# PWR_stage.net
KiCad netlist of a schematic drawn in Altium Designer
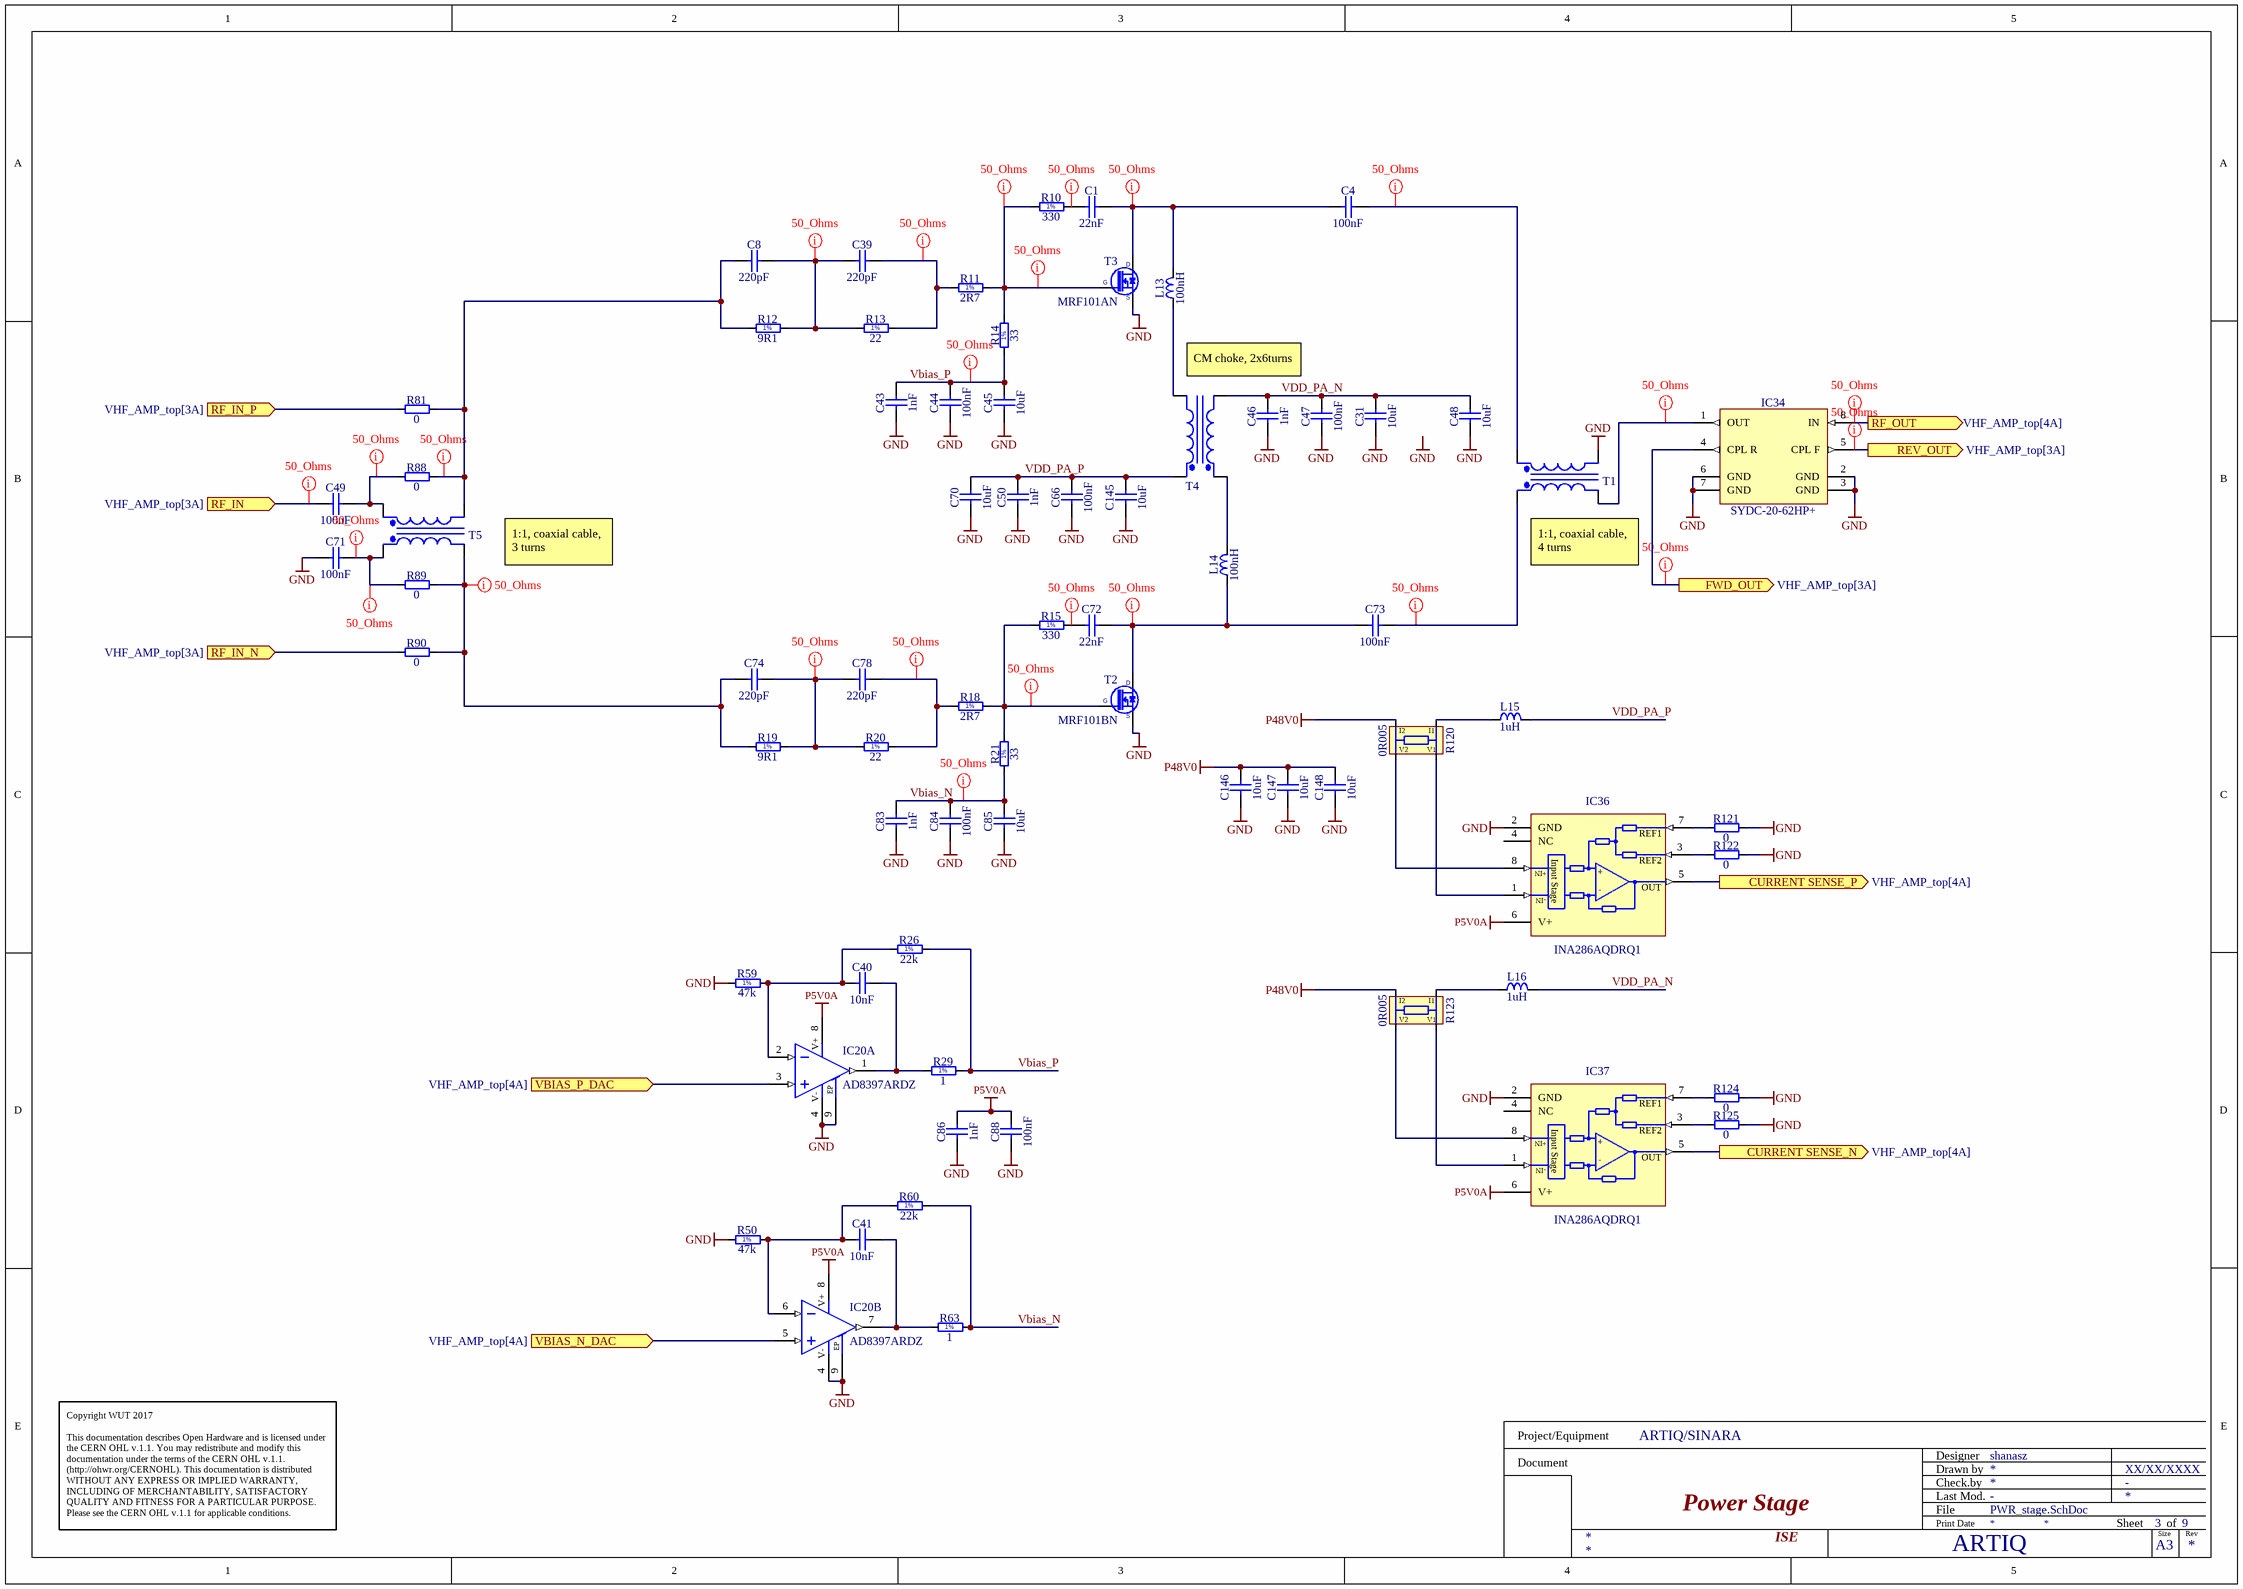
[diagram p0: PWR_stage.SchDoc]

(export (version "E")
  (design (tool "Eeschema 10.0.6"))
  (components
    (comp (ref "C1")
      (value "22nF")
      (footprint "CAPC2012X135N")
      (description "Non-polarised capacitor")
      (fields
        (field (name "PART NUMBER") "CC0805_22NF_50V_10%_X7R")
        (field (name "VOLTAGE") "50V")
        (field (name "AUTHOR") "CERN DEM JLC")
      )
      (libsource (lib "Capacitors") (part "Capacitor - non polarized"))
    )
    (comp (ref "C4")
      (value "100nF")
      (footprint "CAPC3216X140N")
      (description "Non-polarised capacitor")
      (fields
        (field (name "PART NUMBER") "CC1206_100NF_100V_10%_X7R")
        (field (name "VOLTAGE") "100V")
        (field (name "AUTHOR") "CERN DEM JLC")
      )
      (libsource (lib "Capacitors") (part "Capacitor - non polarized"))
    )
    (comp (ref "C8")
      (value "220pF")
      (footprint "CAPC2012X135N")
      (description "Non-polarised capacitor")
      (fields
        (field (name "PART NUMBER") "CC0805_220PF_50V_5%_C0G")
        (field (name "VOLTAGE") "50V")
        (field (name "AUTHOR") "CERN DEM JLC")
      )
      (libsource (lib "Capacitors") (part "Capacitor - non polarized"))
    )
    (comp (ref "C31")
      (value "10uF")
      (footprint "CAPC_TDK_CKG45N")
      (description "Non-polarised capacitor")
      (fields
        (field (name "PART NUMBER") "CC1812_10UF_100V_20%_X7S_TDK_CKG45N")
        (field (name "VOLTAGE") "100V")
        (field (name "AUTHOR") "CERN DEM MR")
      )
      (libsource (lib "Capacitors") (part "Capacitor - non polarized"))
    )
    (comp (ref "C39")
      (value "220pF")
      (footprint "CAPC2012X135N")
      (description "Non-polarised capacitor")
      (fields
        (field (name "PART NUMBER") "CC0805_220PF_50V_5%_C0G")
        (field (name "VOLTAGE") "50V")
        (field (name "AUTHOR") "CERN DEM JLC")
      )
      (libsource (lib "Capacitors") (part "Capacitor - non polarized"))
    )
    (comp (ref "C40")
      (value "10nF")
      (footprint "CAPC1005X55N")
      (description "Non-polarised capacitor")
      (fields
        (field (name "MANUFACTURER PART NUMBER") "CC0402_10NF_16V_10%_X7R")
        (field (name "MANUFACTURER") "GENERIC")
        (field (name "AUTHOR") "CERN DEM JLC")
      )
      (libsource (lib "Capacitors") (part "Capacitor - non polarized"))
    )
    (comp (ref "C41")
      (value "10nF")
      (footprint "CAPC1005X55N")
      (description "Non-polarised capacitor")
      (fields
        (field (name "MANUFACTURER PART NUMBER") "CC0402_10NF_16V_10%_X7R")
        (field (name "MANUFACTURER") "GENERIC")
        (field (name "AUTHOR") "CERN DEM JLC")
      )
      (libsource (lib "Capacitors") (part "Capacitor - non polarized"))
    )
    (comp (ref "C43")
      (value "1nF")
      (footprint "CAPC2012X135N")
      (description "Non-polarised capacitor")
      (fields
        (field (name "PART NUMBER") "CC0805_1NF_50V_5%_C0G")
        (field (name "VOLTAGE") "50V")
        (field (name "AUTHOR") "CERN DEM JLC")
      )
      (libsource (lib "Capacitors") (part "Capacitor - non polarized"))
    )
    (comp (ref "C44")
      (value "100nF")
      (footprint "CAPC3216X140N")
      (description "Non-polarised capacitor")
      (fields
        (field (name "PART NUMBER") "CC1206_100NF_100V_10%_X7R")
        (field (name "VOLTAGE") "100V")
        (field (name "AUTHOR") "CERN DEM JLC")
      )
      (libsource (lib "Capacitors") (part "Capacitor - non polarized"))
    )
    (comp (ref "C45")
      (value "10uF")
      (footprint "CAPC3225X280N")
      (description "Non-polarised capacitor")
      (fields
        (field (name "PART NUMBER") "CC1210_10UF_50V_10%_X7R_YUDEN_UMK325AB7106KMHP")
        (field (name "VOLTAGE") "50V")
        (field (name "AUTHOR") "CERN DEM JLC")
      )
      (libsource (lib "Capacitors") (part "Capacitor - non polarized"))
    )
    (comp (ref "C46")
      (value "1nF")
      (footprint "CAPC2012X135N")
      (description "Non-polarised capacitor")
      (fields
        (field (name "PART NUMBER") "CC0805_1NF_50V_5%_C0G")
        (field (name "VOLTAGE") "50V")
        (field (name "AUTHOR") "CERN DEM JLC")
      )
      (libsource (lib "Capacitors") (part "Capacitor - non polarized"))
    )
    (comp (ref "C47")
      (value "100nF")
      (footprint "CAPC3216X140N")
      (description "Non-polarised capacitor")
      (fields
        (field (name "PART NUMBER") "CC1206_100NF_100V_10%_X7R")
        (field (name "VOLTAGE") "100V")
        (field (name "AUTHOR") "CERN DEM JLC")
      )
      (libsource (lib "Capacitors") (part "Capacitor - non polarized"))
    )
    (comp (ref "C48")
      (value "10uF")
      (footprint "CAPC_TDK_CKG45N")
      (description "Non-polarised capacitor")
      (fields
        (field (name "PART NUMBER") "CC1812_10UF_100V_20%_X7S_TDK_CKG45N")
        (field (name "VOLTAGE") "100V")
        (field (name "AUTHOR") "CERN DEM MR")
      )
      (libsource (lib "Capacitors") (part "Capacitor - non polarized"))
    )
    (comp (ref "C49")
      (value "100nF")
      (footprint "CAPC2012X135N")
      (description "Non-polarised capacitor")
      (fields
        (field (name "PART NUMBER") "CC0805_100NF_50V_10%_X7R")
        (field (name "VOLTAGE") "50V")
        (field (name "AUTHOR") "CERN DEM JLC")
      )
      (libsource (lib "Capacitors") (part "Capacitor - non polarized"))
    )
    (comp (ref "C50")
      (value "1nF")
      (footprint "CAPC2012X135N")
      (description "Non-polarised capacitor")
      (fields
        (field (name "PART NUMBER") "CC0805_1NF_50V_5%_C0G")
        (field (name "VOLTAGE") "50V")
        (field (name "AUTHOR") "CERN DEM JLC")
      )
      (libsource (lib "Capacitors") (part "Capacitor - non polarized"))
    )
    (comp (ref "C66")
      (value "100nF")
      (footprint "CAPC3216X140N")
      (description "Non-polarised capacitor")
      (fields
        (field (name "PART NUMBER") "CC1206_100NF_100V_10%_X7R")
        (field (name "VOLTAGE") "100V")
        (field (name "AUTHOR") "CERN DEM JLC")
      )
      (libsource (lib "Capacitors") (part "Capacitor - non polarized"))
    )
    (comp (ref "C70")
      (value "10uF")
      (footprint "CAPC_TDK_CKG45N")
      (description "Non-polarised capacitor")
      (fields
        (field (name "PART NUMBER") "CC1812_10UF_100V_20%_X7S_TDK_CKG45N")
        (field (name "VOLTAGE") "100V")
        (field (name "AUTHOR") "CERN DEM MR")
      )
      (libsource (lib "Capacitors") (part "Capacitor - non polarized"))
    )
    (comp (ref "C71")
      (value "100nF")
      (footprint "CAPC2012X135N")
      (description "Non-polarised capacitor")
      (fields
        (field (name "PART NUMBER") "CC0805_100NF_50V_10%_X7R")
        (field (name "VOLTAGE") "50V")
        (field (name "AUTHOR") "CERN DEM JLC")
      )
      (libsource (lib "Capacitors") (part "Capacitor - non polarized"))
    )
    (comp (ref "C72")
      (value "22nF")
      (footprint "CAPC2012X135N")
      (description "Non-polarised capacitor")
      (fields
        (field (name "PART NUMBER") "CC0805_22NF_50V_10%_X7R")
        (field (name "VOLTAGE") "50V")
        (field (name "AUTHOR") "CERN DEM JLC")
      )
      (libsource (lib "Capacitors") (part "Capacitor - non polarized"))
    )
    (comp (ref "C73")
      (value "100nF")
      (footprint "CAPC3216X140N")
      (description "Non-polarised capacitor")
      (fields
        (field (name "PART NUMBER") "CC1206_100NF_100V_10%_X7R")
        (field (name "VOLTAGE") "100V")
        (field (name "AUTHOR") "CERN DEM JLC")
      )
      (libsource (lib "Capacitors") (part "Capacitor - non polarized"))
    )
    (comp (ref "C74")
      (value "220pF")
      (footprint "CAPC2012X135N")
      (description "Non-polarised capacitor")
      (fields
        (field (name "PART NUMBER") "CC0805_220PF_50V_5%_C0G")
        (field (name "VOLTAGE") "50V")
        (field (name "AUTHOR") "CERN DEM JLC")
      )
      (libsource (lib "Capacitors") (part "Capacitor - non polarized"))
    )
    (comp (ref "C78")
      (value "220pF")
      (footprint "CAPC2012X135N")
      (description "Non-polarised capacitor")
      (fields
        (field (name "PART NUMBER") "CC0805_220PF_50V_5%_C0G")
        (field (name "VOLTAGE") "50V")
        (field (name "AUTHOR") "CERN DEM JLC")
      )
      (libsource (lib "Capacitors") (part "Capacitor - non polarized"))
    )
    (comp (ref "C83")
      (value "1nF")
      (footprint "CAPC2012X135N")
      (description "Non-polarised capacitor")
      (fields
        (field (name "PART NUMBER") "CC0805_1NF_50V_5%_C0G")
        (field (name "VOLTAGE") "50V")
        (field (name "AUTHOR") "CERN DEM JLC")
      )
      (libsource (lib "Capacitors") (part "Capacitor - non polarized"))
    )
    (comp (ref "C84")
      (value "100nF")
      (footprint "CAPC3216X140N")
      (description "Non-polarised capacitor")
      (fields
        (field (name "PART NUMBER") "CC1206_100NF_100V_10%_X7R")
        (field (name "VOLTAGE") "100V")
        (field (name "AUTHOR") "CERN DEM JLC")
      )
      (libsource (lib "Capacitors") (part "Capacitor - non polarized"))
    )
    (comp (ref "C85")
      (value "10uF")
      (footprint "CAPC3225X280N")
      (description "Non-polarised capacitor")
      (fields
        (field (name "PART NUMBER") "CC1210_10UF_50V_10%_X7R_YUDEN_UMK325AB7106KMHP")
        (field (name "VOLTAGE") "50V")
        (field (name "AUTHOR") "CERN DEM JLC")
      )
      (libsource (lib "Capacitors") (part "Capacitor - non polarized"))
    )
    (comp (ref "C86")
      (value "1nF")
      (footprint "CAPC2012X135N")
      (description "Non-polarised capacitor")
      (fields
        (field (name "PART NUMBER") "CC0805_1NF_50V_5%_C0G")
        (field (name "VOLTAGE") "50V")
        (field (name "AUTHOR") "CERN DEM JLC")
      )
      (libsource (lib "Capacitors") (part "Capacitor - non polarized"))
    )
    (comp (ref "C88")
      (value "100nF")
      (footprint "CAPC2012X135N")
      (description "Non-polarised capacitor")
      (fields
        (field (name "PART NUMBER") "CC0805_100NF_50V_10%_X7R")
        (field (name "VOLTAGE") "50V")
        (field (name "AUTHOR") "CERN DEM JLC")
      )
      (libsource (lib "Capacitors") (part "Capacitor - non polarized"))
    )
    (comp (ref "C145")
      (value "10uF")
      (footprint "CAPC_TDK_CKG45N")
      (description "Non-polarised capacitor")
      (fields
        (field (name "PART NUMBER") "CC1812_10UF_100V_20%_X7S_TDK_CKG45N")
        (field (name "VOLTAGE") "100V")
        (field (name "AUTHOR") "CERN DEM MR")
      )
      (libsource (lib "Capacitors") (part "Capacitor - non polarized"))
    )
    (comp (ref "C146")
      (value "10uF")
      (footprint "CAPC_TDK_CKG45N")
      (description "Non-polarised capacitor")
      (fields
        (field (name "PART NUMBER") "CC1812_10UF_100V_20%_X7S_TDK_CKG45N")
        (field (name "VOLTAGE") "100V")
        (field (name "AUTHOR") "CERN DEM MR")
      )
      (libsource (lib "Capacitors") (part "Capacitor - non polarized"))
    )
    (comp (ref "C147")
      (value "10uF")
      (footprint "CAPC_TDK_CKG45N")
      (description "Non-polarised capacitor")
      (fields
        (field (name "PART NUMBER") "CC1812_10UF_100V_20%_X7S_TDK_CKG45N")
        (field (name "VOLTAGE") "100V")
        (field (name "AUTHOR") "CERN DEM MR")
      )
      (libsource (lib "Capacitors") (part "Capacitor - non polarized"))
    )
    (comp (ref "C148")
      (value "10uF")
      (footprint "CAPC_TDK_CKG45N")
      (description "Non-polarised capacitor")
      (fields
        (field (name "PART NUMBER") "CC1812_10UF_100V_20%_X7S_TDK_CKG45N")
        (field (name "VOLTAGE") "100V")
        (field (name "AUTHOR") "CERN DEM MR")
      )
      (libsource (lib "Capacitors") (part "Capacitor - non polarized"))
    )
    (comp (ref "IC20")
      (value "AD8397ARDZ")
      (footprint "SOIC127P600X175-9N-R241X309")
      (description "Dual Operational Amplifier With Exposed Pad")
      (fields (field (name "MANUFACTURER") "ANALOG DEVICES") (field (name "AUTHOR") "CERN DEM JLC"))
      (libsource (lib "ICs And Semiconductors") (part "Operational Amplifier x2 Type1 EP"))
    )
    (comp (ref "IC34")
      (value "SYDC-20-62HP+")
      (footprint "MINI-CIRCUITS_AH202-1")
      (description "50Ohm, 10 to 540MHz, 25W, 20dB Bi-Directional Coupler")
      (fields (field (name "MANUFACTURER") "MINI-CIRCUITS") (field (name "AUTHOR") "CERN DEM BC"))
      (libsource (lib "ICs And Semiconductors") (part "SYDC-20-62HP+"))
    )
    (comp (ref "IC36")
      (value "INA286AQDRQ1")
      (footprint "SOIC127P600X175-8N")
      (description "80V, Bi-Directional, Low-/High-Side, Voltage Output Current Sense Amplifier")
      (fields (field (name "MANUFACTURER") "TEXAS INSTRUMENTS") (field (name "AUTHOR") "CERN DEM JLC"))
      (libsource (lib "ICs And Semiconductors") (part "INA286"))
    )
    (comp (ref "IC37")
      (value "INA286AQDRQ1")
      (footprint "SOIC127P600X175-8N")
      (description "80V, Bi-Directional, Low-/High-Side, Voltage Output Current Sense Amplifier")
      (fields (field (name "MANUFACTURER") "TEXAS INSTRUMENTS") (field (name "AUTHOR") "CERN DEM JLC"))
      (libsource (lib "ICs And Semiconductors") (part "INA286"))
    )
    (comp (ref "L13")
      (value "100nH")
      (footprint "IND_COILCRAFT_1812SMS")
      (description "Inductor")
      (fields
        (field (name "PART NUMBER") "IND_100NH_5%_COILCRAFT_1812SMS-R10JLC")
        (field (name "POWER") "1.7A")
        (field (name "AUTHOR") "CERN DEM JLC")
      )
      (libsource (lib "Inductors & Transformers") (part "Inductor"))
    )
    (comp (ref "L14")
      (value "100nH")
      (footprint "IND_COILCRAFT_1812SMS")
      (description "Inductor")
      (fields
        (field (name "PART NUMBER") "IND_100NH_5%_COILCRAFT_1812SMS-R10JLC")
        (field (name "POWER") "1.7A")
        (field (name "AUTHOR") "CERN DEM JLC")
      )
      (libsource (lib "Inductors & Transformers") (part "Inductor"))
    )
    (comp (ref "L15")
      (value "1uH")
      (footprint "IND_BOURNS_SRN3015")
      (description "Inductor")
      (fields
        (field (name "PART NUMBER") "IND_1UH_30%_BOURNS_SRN3015")
        (field (name "POWER") "2.35A")
        (field (name "AUTHOR") "CERN DEM JLC")
      )
      (libsource (lib "") (part "Inductor_1"))
    )
    (comp (ref "L16")
      (value "1uH")
      (footprint "IND_BOURNS_SRN3015")
      (description "Inductor")
      (fields
        (field (name "PART NUMBER") "IND_1UH_30%_BOURNS_SRN3015")
        (field (name "POWER") "2.35A")
        (field (name "AUTHOR") "CERN DEM JLC")
      )
      (libsource (lib "") (part "Inductor_1"))
    )
    (comp (ref "R10")
      (value "330")
      (footprint "RESC2012X60N")
      (description "Resistor - 1%")
      (fields
        (field (name "PART NUMBER") "R0805_330R_1%_0.125W_100PPM")
        (field (name "POWER") "0.125W")
        (field (name "AUTHOR") "CERN DEM JLC")
      )
      (libsource (lib "Resistors") (part "Resistor - 1%"))
    )
    (comp (ref "R11")
      (value "2R7")
      (footprint "RESC2012X60N")
      (description "Resistor - 1%")
      (fields
        (field (name "PART NUMBER") "R0805_2R7_1%_0.125W_200PPM")
        (field (name "POWER") "0.125W")
        (field (name "AUTHOR") "CERN DEM JLC")
      )
      (libsource (lib "Resistors") (part "Resistor - 1%"))
    )
    (comp (ref "R12")
      (value "9R1")
      (footprint "RESC2012X60N")
      (description "Resistor - 1%")
      (fields
        (field (name "PART NUMBER") "R0805_9R1_1%_0.125W_200PPM")
        (field (name "POWER") "0.125W")
        (field (name "AUTHOR") "CERN DEM JLC")
      )
      (libsource (lib "Resistors") (part "Resistor - 1%"))
    )
    (comp (ref "R13")
      (value "22")
      (footprint "RESC2012X60N")
      (description "Resistor - 1%")
      (fields
        (field (name "PART NUMBER") "R0805_22R_1%_0.125W_100PPM")
        (field (name "POWER") "0.125W")
        (field (name "AUTHOR") "CERN DEM JLC")
      )
      (libsource (lib "Resistors") (part "Resistor - 1%"))
    )
    (comp (ref "R14")
      (value "33")
      (footprint "RESC2012X60N")
      (description "Resistor - 1%")
      (fields
        (field (name "PART NUMBER") "R0805_33R_1%_0.125W_100PPM")
        (field (name "POWER") "0.125W")
        (field (name "AUTHOR") "CERN DEM JLC")
      )
      (libsource (lib "Resistors") (part "Resistor - 1%"))
    )
    (comp (ref "R15")
      (value "330")
      (footprint "RESC2012X60N")
      (description "Resistor - 1%")
      (fields
        (field (name "PART NUMBER") "R0805_330R_1%_0.125W_100PPM")
        (field (name "POWER") "0.125W")
        (field (name "AUTHOR") "CERN DEM JLC")
      )
      (libsource (lib "Resistors") (part "Resistor - 1%"))
    )
    (comp (ref "R18")
      (value "2R7")
      (footprint "RESC2012X60N")
      (description "Resistor - 1%")
      (fields
        (field (name "PART NUMBER") "R0805_2R7_1%_0.125W_200PPM")
        (field (name "POWER") "0.125W")
        (field (name "AUTHOR") "CERN DEM JLC")
      )
      (libsource (lib "Resistors") (part "Resistor - 1%"))
    )
    (comp (ref "R19")
      (value "9R1")
      (footprint "RESC2012X60N")
      (description "Resistor - 1%")
      (fields
        (field (name "PART NUMBER") "R0805_9R1_1%_0.125W_200PPM")
        (field (name "POWER") "0.125W")
        (field (name "AUTHOR") "CERN DEM JLC")
      )
      (libsource (lib "Resistors") (part "Resistor - 1%"))
    )
    (comp (ref "R20")
      (value "22")
      (footprint "RESC2012X60N")
      (description "Resistor - 1%")
      (fields
        (field (name "PART NUMBER") "R0805_22R_1%_0.125W_100PPM")
        (field (name "POWER") "0.125W")
        (field (name "AUTHOR") "CERN DEM JLC")
      )
      (libsource (lib "Resistors") (part "Resistor - 1%"))
    )
    (comp (ref "R21")
      (value "33")
      (footprint "RESC2012X60N")
      (description "Resistor - 1%")
      (fields
        (field (name "PART NUMBER") "R0805_33R_1%_0.125W_100PPM")
        (field (name "POWER") "0.125W")
        (field (name "AUTHOR") "CERN DEM JLC")
      )
      (libsource (lib "Resistors") (part "Resistor - 1%"))
    )
    (comp (ref "R26")
      (value "22k")
      (footprint "RESC1005X40N")
      (description "Resistor - 1%")
      (fields
        (field (name "PART NUMBER") "R0402_22K_1%_0.0625W_100PPM")
        (field (name "POWER") "0.0625W")
        (field (name "AUTHOR") "CERN DEM JLC")
      )
      (libsource (lib "Resistors") (part "Resistor - 1%"))
    )
    (comp (ref "R29")
      (value "1")
      (footprint "RESC1005X40N")
      (description "Resistor - 1%")
      (fields
        (field (name "PART NUMBER") "R0402_1R_1%_0.0625W_200PPM")
        (field (name "POWER") "0.0625W")
        (field (name "AUTHOR") "CERN DEM JLC")
      )
      (libsource (lib "Resistors") (part "Resistor - 1%"))
    )
    (comp (ref "R50")
      (value "47k")
      (footprint "RESC1005X40N")
      (description "Resistor - 1%")
      (fields
        (field (name "PART NUMBER") "R0402_47K_1%_0.0625W_100PPM")
        (field (name "POWER") "0.0625W")
        (field (name "AUTHOR") "CERN DEM JLC")
      )
      (libsource (lib "Resistors") (part "Resistor - 1%"))
    )
    (comp (ref "R59")
      (value "47k")
      (footprint "RESC1005X40N")
      (description "Resistor - 1%")
      (fields
        (field (name "PART NUMBER") "R0402_47K_1%_0.0625W_100PPM")
        (field (name "POWER") "0.0625W")
        (field (name "AUTHOR") "CERN DEM JLC")
      )
      (libsource (lib "Resistors") (part "Resistor - 1%"))
    )
    (comp (ref "R60")
      (value "22k")
      (footprint "RESC1005X40N")
      (description "Resistor - 1%")
      (fields
        (field (name "PART NUMBER") "R0402_22K_1%_0.0625W_100PPM")
        (field (name "POWER") "0.0625W")
        (field (name "AUTHOR") "CERN DEM JLC")
      )
      (libsource (lib "Resistors") (part "Resistor - 1%"))
    )
    (comp (ref "R63")
      (value "1")
      (footprint "RESC1005X40N")
      (description "Resistor - 1%")
      (fields
        (field (name "PART NUMBER") "R0402_1R_1%_0.0625W_200PPM")
        (field (name "POWER") "0.0625W")
        (field (name "AUTHOR") "CERN DEM JLC")
      )
      (libsource (lib "Resistors") (part "Resistor - 1%"))
    )
    (comp (ref "R81")
      (value "0")
      (footprint "RESC2012X60N")
      (description "Resistor")
      (fields
        (field (name "PART NUMBER") "R0805_0R_JUMPER")
        (field (name "MANUFACTURER") "GENERIC")
        (field (name "AUTHOR") "CERN DEM JLC")
      )
      (libsource (lib "Resistors") (part "Resistor"))
    )
    (comp (ref "R88")
      (value "0")
      (footprint "RESC2012X60N")
      (description "Resistor")
      (fields
        (field (name "PART NUMBER") "R0805_0R_JUMPER")
        (field (name "MANUFACTURER") "GENERIC")
        (field (name "AUTHOR") "CERN DEM JLC")
      )
      (libsource (lib "Resistors") (part "Resistor"))
    )
    (comp (ref "R89")
      (value "0")
      (footprint "RESC2012X60N")
      (description "Resistor")
      (fields
        (field (name "PART NUMBER") "R0805_0R_JUMPER")
        (field (name "MANUFACTURER") "GENERIC")
        (field (name "AUTHOR") "CERN DEM JLC")
      )
      (libsource (lib "Resistors") (part "Resistor"))
    )
    (comp (ref "R90")
      (value "0")
      (footprint "RESC2012X60N")
      (description "Resistor")
      (fields
        (field (name "PART NUMBER") "R0805_0R_JUMPER")
        (field (name "MANUFACTURER") "GENERIC")
        (field (name "AUTHOR") "CERN DEM JLC")
      )
      (libsource (lib "Resistors") (part "Resistor"))
    )
    (comp (ref "R120")
      (value "0R005")
      (footprint "RES_OHMITE_LVK25")
      (description "Power and Current Sensing Resistor")
      (fields
        (field (name "PART NUMBER") "R_0R005_0.5%_2W_100PPM_OHMITE_LVK25")
        (field (name "POWER") "2W")
        (field (name "AUTHOR") "CERN DEM JLC")
      )
      (libsource (lib "Resistors") (part "Current + Voltage Sense Resistor"))
    )
    (comp (ref "R121")
      (value "0")
      (footprint "RESC2012X60N")
      (description "Resistor")
      (fields
        (field (name "PART NUMBER") "R0805_0R_JUMPER")
        (field (name "MANUFACTURER") "GENERIC")
        (field (name "AUTHOR") "CERN DEM JLC")
      )
      (libsource (lib "Resistors") (part "Resistor"))
    )
    (comp (ref "R122")
      (value "0")
      (footprint "RESC2012X60N")
      (description "Resistor")
      (fields
        (field (name "PART NUMBER") "R0805_0R_JUMPER")
        (field (name "MANUFACTURER") "GENERIC")
        (field (name "AUTHOR") "CERN DEM JLC")
      )
      (libsource (lib "Resistors") (part "Resistor"))
    )
    (comp (ref "R123")
      (value "0R005")
      (footprint "RES_OHMITE_LVK25")
      (description "Power and Current Sensing Resistor")
      (fields
        (field (name "PART NUMBER") "R_0R005_0.5%_2W_100PPM_OHMITE_LVK25")
        (field (name "POWER") "2W")
        (field (name "AUTHOR") "CERN DEM JLC")
      )
      (libsource (lib "Resistors") (part "Current + Voltage Sense Resistor"))
    )
    (comp (ref "R124")
      (value "0")
      (footprint "RESC2012X60N")
      (description "Resistor")
      (fields
        (field (name "PART NUMBER") "R0805_0R_JUMPER")
        (field (name "MANUFACTURER") "GENERIC")
        (field (name "AUTHOR") "CERN DEM JLC")
      )
      (libsource (lib "Resistors") (part "Resistor"))
    )
    (comp (ref "R125")
      (value "0")
      (footprint "RESC2012X60N")
      (description "Resistor")
      (fields
        (field (name "PART NUMBER") "R0805_0R_JUMPER")
        (field (name "MANUFACTURER") "GENERIC")
        (field (name "AUTHOR") "CERN DEM JLC")
      )
      (libsource (lib "Resistors") (part "Resistor"))
    )
    (comp (ref "T1")
      (value "Trans Ideal")
      (footprint "Balun_5961000601")
      (description "Transformer (Ideal)")
      (fields (field (name "PUBLISHER") "Altium Limited"))
      (libsource (lib "") (part "Balun_coaxialcable_1"))
    )
    (comp (ref "T2")
      (value "MRF101BN")
      (footprint "TO-220-HFLIP")
      (description "N-CHANNEL MOSFET WITH DIODE")
      (fields
        (field (name "PART NUMBER") "MRF101BN_hflip")
        (field (name "MANUFACTURER") "NXP SEMICONDUCTORS")
        (field (name "AUTHOR") "CERN DEM HF")
      )
      (libsource (lib "ICs And Semiconductors") (part "N-MOSFET-D 1D 2S 3G"))
    )
    (comp (ref "T3")
      (value "MRF101AN")
      (footprint "TO-220-HFLIP")
      (description "N-CHANNEL MOSFET WITH DIODE")
      (fields
        (field (name "PART NUMBER") "MRF101AN_hflip")
        (field (name "MANUFACTURER") "NXP SEMICONDUCTORS")
        (field (name "AUTHOR") "CERN DEM HF")
      )
      (libsource (lib "ICs And Semiconductors") (part "N-MOSFET-D 1G 2S 3D"))
    )
    (comp (ref "T4")
      (value "Trans Ideal")
      (footprint "Balun_5961000601_power")
      (description "Transformer (Ideal)")
      (fields (field (name "PUBLISHER") "Altium Limited"))
      (libsource (lib "VHF_AMP_lib") (part "Balun_coaxialcable"))
    )
    (comp (ref "T5")
      (value "Trans Ideal")
      (footprint "Balun_5943001101")
      (description "Transformer (Ideal)")
      (fields (field (name "PUBLISHER") "Altium Limited"))
      (libsource (lib "") (part "Balun_coaxialcable_1"))
    )
  )
  (nets
    (net (code "1") (name "/CURRENT SENSE_N") (class "Default")
      (node (ref "IC37") (pin "5") (pinfunction "OUT_5") (pintype "output"))
    )
    (net (code "2") (name "/CURRENT SENSE_P") (class "Default")
      (node (ref "IC36") (pin "5") (pinfunction "OUT_5") (pintype "output"))
    )
    (net (code "3") (name "/FWD_OUT") (class "Default")
      (node (ref "IC34") (pin "4") (pinfunction "CPL_R_4") (pintype "output"))
    )
    (net (code "4") (name "/REV_OUT") (class "Default")
      (node (ref "IC34") (pin "5") (pinfunction "CPL_F_5") (pintype "output"))
    )
    (net (code "5") (name "/RF_IN") (class "Default")
      (node (ref "C49") (pin "1") (pinfunction "1_1") (pintype "passive"))
    )
    (net (code "6") (name "/RF_IN_N") (class "Default")
      (node (ref "R90") (pin "1") (pinfunction "1_1") (pintype "passive"))
    )
    (net (code "7") (name "/RF_IN_P") (class "Default")
      (node (ref "R81") (pin "1") (pinfunction "1_1") (pintype "passive"))
    )
    (net (code "8") (name "/RF_OUT") (class "Default")
      (node (ref "IC34") (pin "8") (pinfunction "IN_8") (pintype "input"))
    )
    (net (code "9") (name "/VBIAS_N_DAC") (class "Default")
      (node (ref "IC20") (pin "5") (pinfunction "IN+_5") (pintype "input"))
    )
    (net (code "10") (name "/VBIAS_P_DAC") (class "Default")
      (node (ref "IC20") (pin "3") (pinfunction "IN+_3") (pintype "input"))
    )
    (net (code "11") (name "/VDD_PA_N") (class "Default")
      (node (ref "C31") (pin "2") (pinfunction "2_2") (pintype "passive"))
      (node (ref "C46") (pin "2") (pinfunction "2_2") (pintype "passive"))
      (node (ref "C47") (pin "2") (pinfunction "2_2") (pintype "passive"))
      (node (ref "C48") (pin "2") (pinfunction "2_2") (pintype "passive"))
      (node (ref "L16") (pin "2") (pinfunction "2_2") (pintype "passive"))
      (node (ref "T4") (pin "2") (pinfunction "Pri-_2") (pintype "passive"))
    )
    (net (code "12") (name "/VDD_PA_P") (class "Default")
      (node (ref "C145") (pin "2") (pinfunction "2_2") (pintype "passive"))
      (node (ref "C50") (pin "2") (pinfunction "2_2") (pintype "passive"))
      (node (ref "C66") (pin "2") (pinfunction "2_2") (pintype "passive"))
      (node (ref "C70") (pin "2") (pinfunction "2_2") (pintype "passive"))
      (node (ref "L15") (pin "2") (pinfunction "2_2") (pintype "passive"))
      (node (ref "T4") (pin "3") (pinfunction "Sec+_3") (pintype "passive"))
    )
    (net (code "13") (name "/Vbias_N") (class "Default")
      (node (ref "C83") (pin "2") (pinfunction "2_2") (pintype "passive"))
      (node (ref "C84") (pin "2") (pinfunction "2_2") (pintype "passive"))
      (node (ref "C85") (pin "2") (pinfunction "2_2") (pintype "passive"))
      (node (ref "R21") (pin "1") (pinfunction "1_1") (pintype "passive"))
      (node (ref "R60") (pin "1") (pinfunction "1_1") (pintype "passive"))
      (node (ref "R63") (pin "2") (pinfunction "2_2") (pintype "passive"))
    )
    (net (code "14") (name "/Vbias_P") (class "Default")
      (node (ref "C43") (pin "2") (pinfunction "2_2") (pintype "passive"))
      (node (ref "C44") (pin "2") (pinfunction "2_2") (pintype "passive"))
      (node (ref "C45") (pin "2") (pinfunction "2_2") (pintype "passive"))
      (node (ref "R14") (pin "1") (pinfunction "1_1") (pintype "passive"))
      (node (ref "R26") (pin "1") (pinfunction "1_1") (pintype "passive"))
      (node (ref "R29") (pin "2") (pinfunction "2_2") (pintype "passive"))
    )
    (net (code "15") (name "GND") (class "Default")
      (node (ref "C145") (pin "1") (pinfunction "1_1") (pintype "passive"))
      (node (ref "C146") (pin "1") (pinfunction "1_1") (pintype "passive"))
      (node (ref "C147") (pin "1") (pinfunction "1_1") (pintype "passive"))
      (node (ref "C148") (pin "1") (pinfunction "1_1") (pintype "passive"))
      (node (ref "C31") (pin "1") (pinfunction "1_1") (pintype "passive"))
      (node (ref "C43") (pin "1") (pinfunction "1_1") (pintype "passive"))
      (node (ref "C44") (pin "1") (pinfunction "1_1") (pintype "passive"))
      (node (ref "C45") (pin "1") (pinfunction "1_1") (pintype "passive"))
      (node (ref "C46") (pin "1") (pinfunction "1_1") (pintype "passive"))
      (node (ref "C47") (pin "1") (pinfunction "1_1") (pintype "passive"))
      (node (ref "C48") (pin "1") (pinfunction "1_1") (pintype "passive"))
      (node (ref "C50") (pin "1") (pinfunction "1_1") (pintype "passive"))
      (node (ref "C66") (pin "1") (pinfunction "1_1") (pintype "passive"))
      (node (ref "C70") (pin "1") (pinfunction "1_1") (pintype "passive"))
      (node (ref "C71") (pin "1") (pinfunction "1_1") (pintype "passive"))
      (node (ref "C83") (pin "1") (pinfunction "1_1") (pintype "passive"))
      (node (ref "C84") (pin "1") (pinfunction "1_1") (pintype "passive"))
      (node (ref "C85") (pin "1") (pinfunction "1_1") (pintype "passive"))
      (node (ref "C86") (pin "1") (pinfunction "1_1") (pintype "passive"))
      (node (ref "C88") (pin "1") (pinfunction "1_1") (pintype "passive"))
      (node (ref "IC20") (pin "4") (pinfunction "V-_4") (pintype "power_in"))
      (node (ref "IC20") (pin "9") (pinfunction "Exposed_Pad_9") (pintype "power_in"))
      (node (ref "IC34") (pin "2") (pinfunction "GND_2") (pintype "power_in"))
      (node (ref "IC34") (pin "3") (pinfunction "GND_3") (pintype "power_in"))
      (node (ref "IC34") (pin "6") (pinfunction "GND_6") (pintype "power_in"))
      (node (ref "IC34") (pin "7") (pinfunction "GND_7") (pintype "power_in"))
      (node (ref "IC36") (pin "2") (pinfunction "GND_2") (pintype "power_in"))
      (node (ref "IC37") (pin "2") (pinfunction "GND_2") (pintype "power_in"))
      (node (ref "R121") (pin "2") (pinfunction "2_2") (pintype "passive"))
      (node (ref "R122") (pin "2") (pinfunction "2_2") (pintype "passive"))
      (node (ref "R124") (pin "2") (pinfunction "2_2") (pintype "passive"))
      (node (ref "R125") (pin "2") (pinfunction "2_2") (pintype "passive"))
      (node (ref "R50") (pin "2") (pinfunction "2_2") (pintype "passive"))
      (node (ref "R59") (pin "2") (pinfunction "2_2") (pintype "passive"))
      (node (ref "T1") (pin "2") (pinfunction "Pri-_2") (pintype "passive"))
      (node (ref "T2") (pin "2") (pinfunction "S_2") (pintype "passive"))
      (node (ref "T3") (pin "2") (pinfunction "S_2") (pintype "passive"))
    )
    (net (code "16") (name "Net-(C1-Pad1)") (class "Default")
      (node (ref "C1") (pin "1") (pinfunction "1_1") (pintype "passive"))
      (node (ref "R10") (pin "2") (pinfunction "2_2") (pintype "passive"))
    )
    (net (code "17") (name "Net-(C39-Pad1)") (class "Default")
      (node (ref "C39") (pin "1") (pinfunction "1_1") (pintype "passive"))
      (node (ref "C8") (pin "2") (pinfunction "2_2") (pintype "passive"))
      (node (ref "R12") (pin "2") (pinfunction "2_2") (pintype "passive"))
      (node (ref "R13") (pin "1") (pinfunction "1_1") (pintype "passive"))
    )
    (net (code "18") (name "Net-(C39-Pad2)") (class "Default")
      (node (ref "C39") (pin "2") (pinfunction "2_2") (pintype "passive"))
      (node (ref "R11") (pin "1") (pinfunction "1_1") (pintype "passive"))
      (node (ref "R13") (pin "2") (pinfunction "2_2") (pintype "passive"))
    )
    (net (code "19") (name "Net-(C72-Pad1)") (class "Default")
      (node (ref "C72") (pin "1") (pinfunction "1_1") (pintype "passive"))
      (node (ref "R15") (pin "2") (pinfunction "2_2") (pintype "passive"))
    )
    (net (code "20") (name "Net-(C74-Pad2)") (class "Default")
      (node (ref "C74") (pin "2") (pinfunction "2_2") (pintype "passive"))
      (node (ref "C78") (pin "1") (pinfunction "1_1") (pintype "passive"))
      (node (ref "R19") (pin "2") (pinfunction "2_2") (pintype "passive"))
      (node (ref "R20") (pin "1") (pinfunction "1_1") (pintype "passive"))
    )
    (net (code "21") (name "Net-(C78-Pad2)") (class "Default")
      (node (ref "C78") (pin "2") (pinfunction "2_2") (pintype "passive"))
      (node (ref "R18") (pin "1") (pinfunction "1_1") (pintype "passive"))
      (node (ref "R20") (pin "2") (pinfunction "2_2") (pintype "passive"))
    )
    (net (code "22") (name "Net-(IC20A-IN-)") (class "Default")
      (node (ref "C40") (pin "1") (pinfunction "1_1") (pintype "passive"))
      (node (ref "IC20") (pin "2") (pinfunction "IN-_2") (pintype "input"))
      (node (ref "R26") (pin "2") (pinfunction "2_2") (pintype "passive"))
      (node (ref "R59") (pin "1") (pinfunction "1_1") (pintype "passive"))
    )
    (net (code "23") (name "Net-(IC20A-OUT)") (class "Default")
      (node (ref "C40") (pin "2") (pinfunction "2_2") (pintype "passive"))
      (node (ref "IC20") (pin "1") (pinfunction "OUT_1") (pintype "output"))
      (node (ref "R29") (pin "1") (pinfunction "1_1") (pintype "passive"))
    )
    (net (code "24") (name "Net-(IC20B-IN-)") (class "Default")
      (node (ref "C41") (pin "1") (pinfunction "1_1") (pintype "passive"))
      (node (ref "IC20") (pin "6") (pinfunction "IN-_6") (pintype "input"))
      (node (ref "R50") (pin "1") (pinfunction "1_1") (pintype "passive"))
      (node (ref "R60") (pin "2") (pinfunction "2_2") (pintype "passive"))
    )
    (net (code "25") (name "Net-(IC20B-OUT)") (class "Default")
      (node (ref "C41") (pin "2") (pinfunction "2_2") (pintype "passive"))
      (node (ref "IC20") (pin "7") (pinfunction "OUT_7") (pintype "output"))
      (node (ref "R63") (pin "1") (pinfunction "1_1") (pintype "passive"))
    )
    (net (code "26") (name "Net-(IC34-OUT)") (class "Default")
      (node (ref "IC34") (pin "1") (pinfunction "OUT_1") (pintype "output"))
      (node (ref "T1") (pin "4") (pinfunction "Sec-_4") (pintype "passive"))
    )
    (net (code "27") (name "Net-(IC36-+IN)") (class "Default")
      (node (ref "IC36") (pin "8") (pinfunction "+IN_8") (pintype "input"))
      (node (ref "R120") (pin "V2") (pinfunction "V2_V2") (pintype "passive"))
    )
    (net (code "28") (name "Net-(IC36--IN)") (class "Default")
      (node (ref "IC36") (pin "1") (pinfunction "-IN_1") (pintype "input"))
      (node (ref "R120") (pin "V1") (pinfunction "V1_V1") (pintype "passive"))
    )
    (net (code "29") (name "Net-(IC36-REF1)") (class "Default")
      (node (ref "IC36") (pin "7") (pinfunction "REF1_7") (pintype "input"))
      (node (ref "R121") (pin "1") (pinfunction "1_1") (pintype "passive"))
    )
    (net (code "30") (name "Net-(IC36-REF2)") (class "Default")
      (node (ref "IC36") (pin "3") (pinfunction "REF2_3") (pintype "input"))
      (node (ref "R122") (pin "1") (pinfunction "1_1") (pintype "passive"))
    )
    (net (code "31") (name "Net-(IC37-+IN)") (class "Default")
      (node (ref "IC37") (pin "8") (pinfunction "+IN_8") (pintype "input"))
      (node (ref "R123") (pin "V2") (pinfunction "V2_V2") (pintype "passive"))
    )
    (net (code "32") (name "Net-(IC37--IN)") (class "Default")
      (node (ref "IC37") (pin "1") (pinfunction "-IN_1") (pintype "input"))
      (node (ref "R123") (pin "V1") (pinfunction "V1_V1") (pintype "passive"))
    )
    (net (code "33") (name "Net-(IC37-REF1)") (class "Default")
      (node (ref "IC37") (pin "7") (pinfunction "REF1_7") (pintype "input"))
      (node (ref "R124") (pin "1") (pinfunction "1_1") (pintype "passive"))
    )
    (net (code "34") (name "Net-(IC37-REF2)") (class "Default")
      (node (ref "IC37") (pin "3") (pinfunction "REF2_3") (pintype "input"))
      (node (ref "R125") (pin "1") (pinfunction "1_1") (pintype "passive"))
    )
    (net (code "35") (name "Net-(L15-Pad1)") (class "Default")
      (node (ref "L15") (pin "1") (pinfunction "1_1") (pintype "passive"))
      (node (ref "R120") (pin "I1") (pinfunction "I1_I1") (pintype "passive"))
    )
    (net (code "36") (name "Net-(L16-Pad1)") (class "Default")
      (node (ref "L16") (pin "1") (pinfunction "1_1") (pintype "passive"))
      (node (ref "R123") (pin "I1") (pinfunction "I1_I1") (pintype "passive"))
    )
    (net (code "37") (name "Net-(T1-Pri+)") (class "Default")
      (node (ref "C4") (pin "2") (pinfunction "2_2") (pintype "passive"))
      (node (ref "T1") (pin "1") (pinfunction "Pri+_1") (pintype "passive"))
    )
    (net (code "38") (name "Net-(T1-Sec+)") (class "Default")
      (node (ref "C73") (pin "2") (pinfunction "2_2") (pintype "passive"))
      (node (ref "T1") (pin "3") (pinfunction "Sec+_3") (pintype "passive"))
    )
    (net (code "39") (name "Net-(T2-D)") (class "Default")
      (node (ref "C72") (pin "2") (pinfunction "2_2") (pintype "passive"))
      (node (ref "C73") (pin "1") (pinfunction "1_1") (pintype "passive"))
      (node (ref "L14") (pin "1") (pinfunction "1_1") (pintype "passive"))
      (node (ref "T2") (pin "1") (pinfunction "D_1") (pintype "passive"))
    )
    (net (code "40") (name "Net-(T2-G)") (class "Default")
      (node (ref "R15") (pin "1") (pinfunction "1_1") (pintype "passive"))
      (node (ref "R18") (pin "2") (pinfunction "2_2") (pintype "passive"))
      (node (ref "R21") (pin "2") (pinfunction "2_2") (pintype "passive"))
      (node (ref "T2") (pin "3") (pinfunction "G_3") (pintype "passive"))
    )
    (net (code "41") (name "Net-(T3-D)") (class "Default")
      (node (ref "C1") (pin "2") (pinfunction "2_2") (pintype "passive"))
      (node (ref "C4") (pin "1") (pinfunction "1_1") (pintype "passive"))
      (node (ref "L13") (pin "2") (pinfunction "2_2") (pintype "passive"))
      (node (ref "T3") (pin "3") (pinfunction "D_3") (pintype "passive"))
    )
    (net (code "42") (name "Net-(T3-G)") (class "Default")
      (node (ref "R10") (pin "1") (pinfunction "1_1") (pintype "passive"))
      (node (ref "R11") (pin "2") (pinfunction "2_2") (pintype "passive"))
      (node (ref "R14") (pin "2") (pinfunction "2_2") (pintype "passive"))
      (node (ref "T3") (pin "1") (pinfunction "G_1") (pintype "passive"))
    )
    (net (code "43") (name "Net-(T4-Pri+)") (class "Default")
      (node (ref "L14") (pin "2") (pinfunction "2_2") (pintype "passive"))
      (node (ref "T4") (pin "1") (pinfunction "Pri+_1") (pintype "passive"))
    )
    (net (code "44") (name "Net-(T4-Sec-)") (class "Default")
      (node (ref "L13") (pin "1") (pinfunction "1_1") (pintype "passive"))
      (node (ref "T4") (pin "4") (pinfunction "Sec-_4") (pintype "passive"))
    )
    (net (code "45") (name "Net-(T5-Pri+)") (class "Default")
      (node (ref "C49") (pin "2") (pinfunction "2_2") (pintype "passive"))
      (node (ref "R88") (pin "1") (pinfunction "1_1") (pintype "passive"))
      (node (ref "T5") (pin "1") (pinfunction "Pri+_1") (pintype "passive"))
    )
    (net (code "46") (name "Net-(T5-Pri-)") (class "Default")
      (node (ref "C8") (pin "1") (pinfunction "1_1") (pintype "passive"))
      (node (ref "R12") (pin "1") (pinfunction "1_1") (pintype "passive"))
      (node (ref "R81") (pin "2") (pinfunction "2_2") (pintype "passive"))
      (node (ref "R88") (pin "2") (pinfunction "2_2") (pintype "passive"))
      (node (ref "T5") (pin "2") (pinfunction "Pri-_2") (pintype "passive"))
    )
    (net (code "47") (name "Net-(T5-Sec+)") (class "Default")
      (node (ref "C71") (pin "2") (pinfunction "2_2") (pintype "passive"))
      (node (ref "R89") (pin "1") (pinfunction "1_1") (pintype "passive"))
      (node (ref "T5") (pin "3") (pinfunction "Sec+_3") (pintype "passive"))
    )
    (net (code "48") (name "Net-(T5-Sec-)") (class "Default")
      (node (ref "C74") (pin "1") (pinfunction "1_1") (pintype "passive"))
      (node (ref "R19") (pin "1") (pinfunction "1_1") (pintype "passive"))
      (node (ref "R89") (pin "2") (pinfunction "2_2") (pintype "passive"))
      (node (ref "R90") (pin "2") (pinfunction "2_2") (pintype "passive"))
      (node (ref "T5") (pin "4") (pinfunction "Sec-_4") (pintype "passive"))
    )
    (net (code "49") (name "P5V0A") (class "Default")
      (node (ref "C86") (pin "2") (pinfunction "2_2") (pintype "passive"))
      (node (ref "C88") (pin "2") (pinfunction "2_2") (pintype "passive"))
      (node (ref "IC20") (pin "8") (pinfunction "V+_8") (pintype "power_in"))
      (node (ref "IC36") (pin "6") (pinfunction "V+_6") (pintype "power_in"))
      (node (ref "IC37") (pin "6") (pinfunction "V+_6") (pintype "power_in"))
    )
    (net (code "50") (name "P48V0") (class "Default")
      (node (ref "C146") (pin "2") (pinfunction "2_2") (pintype "passive"))
      (node (ref "C147") (pin "2") (pinfunction "2_2") (pintype "passive"))
      (node (ref "C148") (pin "2") (pinfunction "2_2") (pintype "passive"))
      (node (ref "R120") (pin "I2") (pinfunction "I2_I2") (pintype "passive"))
      (node (ref "R123") (pin "I2") (pinfunction "I2_I2") (pintype "passive"))
    )
    (net (code "51") (name "unconnected-(IC36-NC-Pad4)") (class "Default")
      (node (ref "IC36") (pin "4") (pinfunction "NC_4") (pintype "passive"))
    )
    (net (code "52") (name "unconnected-(IC37-NC-Pad4)") (class "Default")
      (node (ref "IC37") (pin "4") (pinfunction "NC_4") (pintype "passive"))
    )
  )
)
